# 05-Switch_SFP_CM4_RJ45.net
KiCad netlist of a schematic drawn in Altium Designer
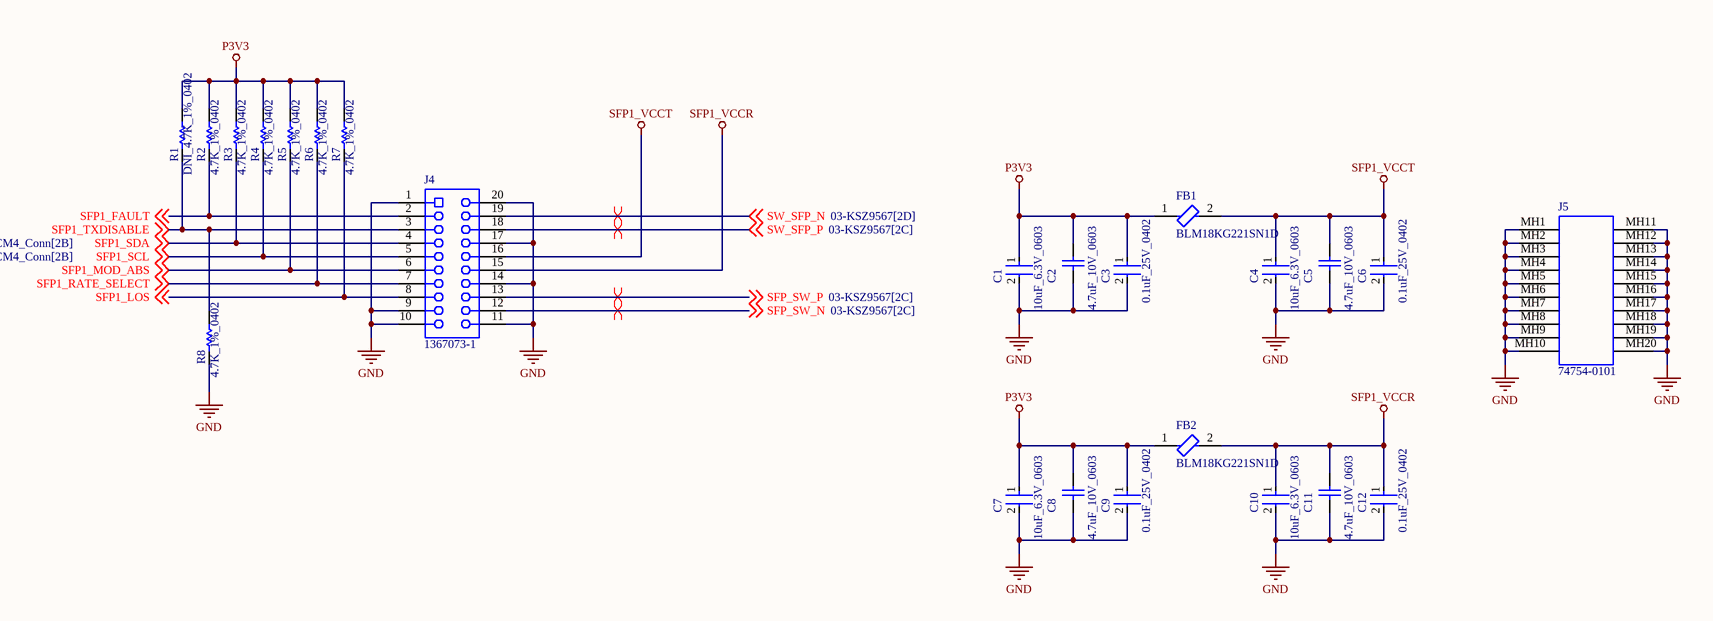
[diagram p0: 05-Switch_SFP_CM4_RJ45.SchDoc]

(export (version "E")
  (design (tool "Eeschema 10.0.6"))
  (components
    (comp (ref "C1")
      (value "10uF_6.3V_0603")
      (footprint "FP-C0603C106M9PACTU-MFG")
      (description "CAP CER 10UF 6.3V X5R 0603")
      (fields
        (field (name "MANUFACTURER PART NUMBER") "C0603C106M9PACTU")
        (field (name "MANUFACTURER") "Kemet")
      )
      (libsource (lib "Altium Content Vault") (part "b4654b650e69147ec39a6b967a45e02"))
    )
    (comp (ref "C2")
      (value "4.7uF_10V_0603")
      (footprint "CAPC1608X87X35NL15T15")
      (fields (field (name "PART NUMBER") "C0603C475K8PACTU") (field (name "MANUFACTURER") "Kemet"))
      (libsource (lib "Altium Content Vault") (part "CAP"))
    )
    (comp (ref "C3")
      (value "0.1uF_25V_0402")
      (footprint "FP-0402-L_1_0_1-W_0_5_0_1-IPC_C")
      (description "General Purpose Ceramic Capacitor, 0402, 100nF, 10%, X7R, 15%, 25V")
      (fields (field (name "VOLTAGE") "25V") (field (name "TOLERANCE") "10%"))
      (libsource (lib "Altium Content Vault") (part "b4654b650e69147ec39a6b967a45e02"))
    )
    (comp (ref "C4")
      (value "10uF_6.3V_0603")
      (footprint "FP-C0603C106M9PACTU-MFG")
      (description "CAP CER 10UF 6.3V X5R 0603")
      (fields
        (field (name "MANUFACTURER PART NUMBER") "C0603C106M9PACTU")
        (field (name "MANUFACTURER") "Kemet")
      )
      (libsource (lib "Altium Content Vault") (part "b4654b650e69147ec39a6b967a45e02"))
    )
    (comp (ref "C5")
      (value "4.7uF_10V_0603")
      (footprint "CAPC1608X87X35NL15T15")
      (fields (field (name "PART NUMBER") "C0603C475K8PACTU") (field (name "MANUFACTURER") "Kemet"))
      (libsource (lib "Altium Content Vault") (part "CAP"))
    )
    (comp (ref "C6")
      (value "0.1uF_25V_0402")
      (footprint "FP-0402-L_1_0_1-W_0_5_0_1-IPC_C")
      (description "General Purpose Ceramic Capacitor, 0402, 100nF, 10%, X7R, 15%, 25V")
      (fields (field (name "VOLTAGE") "25V") (field (name "TOLERANCE") "10%"))
      (libsource (lib "Altium Content Vault") (part "b4654b650e69147ec39a6b967a45e02"))
    )
    (comp (ref "C7")
      (value "10uF_6.3V_0603")
      (footprint "FP-C0603C106M9PACTU-MFG")
      (description "CAP CER 10UF 6.3V X5R 0603")
      (fields
        (field (name "MANUFACTURER PART NUMBER") "C0603C106M9PACTU")
        (field (name "MANUFACTURER") "Kemet")
      )
      (libsource (lib "Altium Content Vault") (part "b4654b650e69147ec39a6b967a45e02"))
    )
    (comp (ref "C8")
      (value "4.7uF_10V_0603")
      (footprint "CAPC1608X87X35NL15T15")
      (fields (field (name "PART NUMBER") "C0603C475K8PACTU") (field (name "MANUFACTURER") "Kemet"))
      (libsource (lib "Altium Content Vault") (part "CAP"))
    )
    (comp (ref "C9")
      (value "0.1uF_25V_0402")
      (footprint "FP-0402-L_1_0_1-W_0_5_0_1-IPC_C")
      (description "General Purpose Ceramic Capacitor, 0402, 100nF, 10%, X7R, 15%, 25V")
      (fields (field (name "VOLTAGE") "25V") (field (name "TOLERANCE") "10%"))
      (libsource (lib "Altium Content Vault") (part "b4654b650e69147ec39a6b967a45e02"))
    )
    (comp (ref "C10")
      (value "10uF_6.3V_0603")
      (footprint "FP-C0603C106M9PACTU-MFG")
      (description "CAP CER 10UF 6.3V X5R 0603")
      (fields
        (field (name "MANUFACTURER PART NUMBER") "C0603C106M9PACTU")
        (field (name "MANUFACTURER") "Kemet")
      )
      (libsource (lib "Altium Content Vault") (part "b4654b650e69147ec39a6b967a45e02"))
    )
    (comp (ref "C11")
      (value "4.7uF_10V_0603")
      (footprint "CAPC1608X87X35NL15T15")
      (fields (field (name "PART NUMBER") "C0603C475K8PACTU") (field (name "MANUFACTURER") "Kemet"))
      (libsource (lib "Altium Content Vault") (part "CAP"))
    )
    (comp (ref "C12")
      (value "0.1uF_25V_0402")
      (footprint "FP-0402-L_1_0_1-W_0_5_0_1-IPC_C")
      (description "General Purpose Ceramic Capacitor, 0402, 100nF, 10%, X7R, 15%, 25V")
      (fields (field (name "VOLTAGE") "25V") (field (name "TOLERANCE") "10%"))
      (libsource (lib "Altium Content Vault") (part "b4654b650e69147ec39a6b967a45e02"))
    )
    (comp (ref "FB1")
      (value "BLM18KG221SN1D")
      (footprint "FP-BLM18-0_15-t0_8-IPC_B")
      (description "Chip Ferrite Bead, 0603, 220Ω @ 100MHz, 0.05Ω, 25%, 2.2A")
      (fields (field (name "TOLERANCE") "25%"))
      (libsource (lib "Altium Content Vault") (part "5f30dd21d616792df468990f7003faa"))
    )
    (comp (ref "FB2")
      (value "BLM18KG221SN1D")
      (footprint "FP-BLM18-0_15-t0_8-IPC_B")
      (description "Chip Ferrite Bead, 0603, 220Ω @ 100MHz, 0.05Ω, 25%, 2.2A")
      (fields (field (name "TOLERANCE") "25%"))
      (libsource (lib "Altium Content Vault") (part "5f30dd21d616792df468990f7003faa"))
    )
    (comp (ref "J4")
      (value "1367073-1")
      (footprint "TECO-1367073-1_V")
      (fields (field (name "MANUFACTURER") "TE Connectivity"))
      (libsource (lib "Altium Content Vault") (part "CN-2P-F-R20_B"))
    )
    (comp (ref "J5")
      (value "74754-0101")
      (footprint "MOLX-74754-0101_V")
      (description "SFP+ Cage, Single Port, Height 10.85 mm, Tail Height 3.05 mm, -40 to 85 degC, RoHS, Tray")
      (libsource (lib "Altium Content Vault") (part "MOLX-74754-0101"))
    )
    (comp (ref "R1")
      (value "DNI_4.7K_1%_0402")
      (footprint "RESC1005X40X25NL10T10")
      (fields (field (name "MANUFACTURER") "Bourns") (field (name "PART NUMBER") "CR0402-FX-4701GLF"))
      (libsource (lib "Altium Content Vault") (part "RES"))
    )
    (comp (ref "R2")
      (value "4.7K_1%_0402")
      (footprint "RESC1005X40X25NL10T10")
      (fields (field (name "MANUFACTURER") "Bourns") (field (name "PART NUMBER") "CR0402-FX-4701GLF"))
      (libsource (lib "Altium Content Vault") (part "RES"))
    )
    (comp (ref "R3")
      (value "4.7K_1%_0402")
      (footprint "RESC1005X40X25NL10T10")
      (fields (field (name "MANUFACTURER") "Bourns") (field (name "PART NUMBER") "CR0402-FX-4701GLF"))
      (libsource (lib "Altium Content Vault") (part "RES"))
    )
    (comp (ref "R4")
      (value "4.7K_1%_0402")
      (footprint "RESC1005X40X25NL10T10")
      (fields (field (name "MANUFACTURER") "Bourns") (field (name "PART NUMBER") "CR0402-FX-4701GLF"))
      (libsource (lib "Altium Content Vault") (part "RES"))
    )
    (comp (ref "R5")
      (value "4.7K_1%_0402")
      (footprint "RESC1005X40X25NL10T10")
      (fields (field (name "MANUFACTURER") "Bourns") (field (name "PART NUMBER") "CR0402-FX-4701GLF"))
      (libsource (lib "Altium Content Vault") (part "RES"))
    )
    (comp (ref "R6")
      (value "4.7K_1%_0402")
      (footprint "RESC1005X40X25NL10T10")
      (fields (field (name "MANUFACTURER") "Bourns") (field (name "PART NUMBER") "CR0402-FX-4701GLF"))
      (libsource (lib "Altium Content Vault") (part "RES"))
    )
    (comp (ref "R7")
      (value "4.7K_1%_0402")
      (footprint "RESC1005X40X25NL10T10")
      (fields (field (name "MANUFACTURER") "Bourns") (field (name "PART NUMBER") "CR0402-FX-4701GLF"))
      (libsource (lib "Altium Content Vault") (part "RES"))
    )
    (comp (ref "R8")
      (value "4.7K_1%_0402")
      (footprint "RESC1005X40X25NL10T10")
      (fields (field (name "MANUFACTURER") "Bourns") (field (name "PART NUMBER") "CR0402-FX-4701GLF"))
      (libsource (lib "Altium Content Vault") (part "RES"))
    )
  )
  (nets
    (net (code "1") (name "GND") (class "Default")
      (node (ref "C1") (pin "2") (pinfunction "2_2") (pintype "passive"))
      (node (ref "C10") (pin "2") (pinfunction "2_2") (pintype "passive"))
      (node (ref "C11") (pin "1") (pinfunction "1_1") (pintype "passive"))
      (node (ref "C12") (pin "2") (pinfunction "2_2") (pintype "passive"))
      (node (ref "C2") (pin "1") (pinfunction "1_1") (pintype "passive"))
      (node (ref "C3") (pin "2") (pinfunction "2_2") (pintype "passive"))
      (node (ref "C4") (pin "2") (pinfunction "2_2") (pintype "passive"))
      (node (ref "C5") (pin "1") (pinfunction "1_1") (pintype "passive"))
      (node (ref "C6") (pin "2") (pinfunction "2_2") (pintype "passive"))
      (node (ref "C7") (pin "2") (pinfunction "2_2") (pintype "passive"))
      (node (ref "C8") (pin "1") (pinfunction "1_1") (pintype "passive"))
      (node (ref "C9") (pin "2") (pinfunction "2_2") (pintype "passive"))
      (node (ref "J4") (pin "1") (pinfunction "1_1") (pintype "passive"))
      (node (ref "J4") (pin "10") (pinfunction "10_10") (pintype "passive"))
      (node (ref "J4") (pin "11") (pinfunction "11_11") (pintype "passive"))
      (node (ref "J4") (pin "14") (pinfunction "14_14") (pintype "passive"))
      (node (ref "J4") (pin "17") (pinfunction "17_17") (pintype "passive"))
      (node (ref "J4") (pin "20") (pinfunction "20_20") (pintype "passive"))
      (node (ref "J4") (pin "9") (pinfunction "9_9") (pintype "passive"))
      (node (ref "J5") (pin "MH1") (pinfunction "MH1_MH1") (pintype "passive"))
      (node (ref "J5") (pin "MH10") (pinfunction "MH10_MH10") (pintype "passive"))
      (node (ref "J5") (pin "MH11") (pinfunction "MH11_MH11") (pintype "passive"))
      (node (ref "J5") (pin "MH12") (pinfunction "MH12_MH12") (pintype "passive"))
      (node (ref "J5") (pin "MH13") (pinfunction "MH13_MH13") (pintype "passive"))
      (node (ref "J5") (pin "MH14") (pinfunction "MH14_MH14") (pintype "passive"))
      (node (ref "J5") (pin "MH15") (pinfunction "MH15_MH15") (pintype "passive"))
      (node (ref "J5") (pin "MH16") (pinfunction "MH16_MH16") (pintype "passive"))
      (node (ref "J5") (pin "MH17") (pinfunction "MH17_MH17") (pintype "passive"))
      (node (ref "J5") (pin "MH18") (pinfunction "MH18_MH18") (pintype "passive"))
      (node (ref "J5") (pin "MH19") (pinfunction "MH19_MH19") (pintype "passive"))
      (node (ref "J5") (pin "MH2") (pinfunction "MH2_MH2") (pintype "passive"))
      (node (ref "J5") (pin "MH20") (pinfunction "MH20_MH20") (pintype "passive"))
      (node (ref "J5") (pin "MH3") (pinfunction "MH3_MH3") (pintype "passive"))
      (node (ref "J5") (pin "MH4") (pinfunction "MH4_MH4") (pintype "passive"))
      (node (ref "J5") (pin "MH5") (pinfunction "MH5_MH5") (pintype "passive"))
      (node (ref "J5") (pin "MH6") (pinfunction "MH6_MH6") (pintype "passive"))
      (node (ref "J5") (pin "MH7") (pinfunction "MH7_MH7") (pintype "passive"))
      (node (ref "J5") (pin "MH8") (pinfunction "MH8_MH8") (pintype "passive"))
      (node (ref "J5") (pin "MH9") (pinfunction "MH9_MH9") (pintype "passive"))
      (node (ref "R8") (pin "2") (pinfunction "2_2") (pintype "passive"))
    )
    (net (code "2") (name "P3V3") (class "Default")
      (node (ref "C1") (pin "1") (pinfunction "1_1") (pintype "passive"))
      (node (ref "C2") (pin "2") (pinfunction "2_2") (pintype "passive"))
      (node (ref "C3") (pin "1") (pinfunction "1_1") (pintype "passive"))
      (node (ref "C7") (pin "1") (pinfunction "1_1") (pintype "passive"))
      (node (ref "C8") (pin "2") (pinfunction "2_2") (pintype "passive"))
      (node (ref "C9") (pin "1") (pinfunction "1_1") (pintype "passive"))
      (node (ref "FB1") (pin "1") (pinfunction "1_1") (pintype "passive"))
      (node (ref "FB2") (pin "1") (pinfunction "1_1") (pintype "passive"))
      (node (ref "R1") (pin "1") (pinfunction "1_1") (pintype "passive"))
      (node (ref "R2") (pin "1") (pinfunction "1_1") (pintype "passive"))
      (node (ref "R3") (pin "1") (pinfunction "1_1") (pintype "passive"))
      (node (ref "R4") (pin "1") (pinfunction "1_1") (pintype "passive"))
      (node (ref "R5") (pin "1") (pinfunction "1_1") (pintype "passive"))
      (node (ref "R6") (pin "1") (pinfunction "1_1") (pintype "passive"))
      (node (ref "R7") (pin "1") (pinfunction "1_1") (pintype "passive"))
    )
    (net (code "3") (name "SFP1_FAULT") (class "Default")
      (node (ref "J4") (pin "2") (pinfunction "2_2") (pintype "passive"))
      (node (ref "R2") (pin "2") (pinfunction "2_2") (pintype "passive"))
    )
    (net (code "4") (name "SFP1_LOS") (class "Default")
      (node (ref "J4") (pin "8") (pinfunction "8_8") (pintype "passive"))
      (node (ref "R7") (pin "2") (pinfunction "2_2") (pintype "passive"))
    )
    (net (code "5") (name "SFP1_MOD_ABS") (class "Default")
      (node (ref "J4") (pin "6") (pinfunction "6_6") (pintype "passive"))
      (node (ref "R5") (pin "2") (pinfunction "2_2") (pintype "passive"))
    )
    (net (code "6") (name "SFP1_RATE_SELECT") (class "Default")
      (node (ref "J4") (pin "7") (pinfunction "7_7") (pintype "passive"))
      (node (ref "R6") (pin "2") (pinfunction "2_2") (pintype "passive"))
    )
    (net (code "7") (name "SFP1_SCL") (class "Default")
      (node (ref "J4") (pin "5") (pinfunction "5_5") (pintype "passive"))
      (node (ref "R4") (pin "2") (pinfunction "2_2") (pintype "passive"))
    )
    (net (code "8") (name "SFP1_SDA") (class "Default")
      (node (ref "J4") (pin "4") (pinfunction "4_4") (pintype "passive"))
      (node (ref "R3") (pin "2") (pinfunction "2_2") (pintype "passive"))
    )
    (net (code "9") (name "SFP1_TXDISABLE") (class "Default")
      (node (ref "J4") (pin "3") (pinfunction "3_3") (pintype "passive"))
      (node (ref "R1") (pin "2") (pinfunction "2_2") (pintype "passive"))
      (node (ref "R8") (pin "1") (pinfunction "1_1") (pintype "passive"))
    )
    (net (code "10") (name "SFP1_VCCR") (class "Default")
      (node (ref "C10") (pin "1") (pinfunction "1_1") (pintype "passive"))
      (node (ref "C11") (pin "2") (pinfunction "2_2") (pintype "passive"))
      (node (ref "C12") (pin "1") (pinfunction "1_1") (pintype "passive"))
      (node (ref "FB2") (pin "2") (pinfunction "2_2") (pintype "passive"))
      (node (ref "J4") (pin "15") (pinfunction "15_15") (pintype "passive"))
    )
    (net (code "11") (name "SFP1_VCCT") (class "Default")
      (node (ref "C4") (pin "1") (pinfunction "1_1") (pintype "passive"))
      (node (ref "C5") (pin "2") (pinfunction "2_2") (pintype "passive"))
      (node (ref "C6") (pin "1") (pinfunction "1_1") (pintype "passive"))
      (node (ref "FB1") (pin "2") (pinfunction "2_2") (pintype "passive"))
      (node (ref "J4") (pin "16") (pinfunction "16_16") (pintype "passive"))
    )
    (net (code "12") (name "SFP_SW_N") (class "Default")
      (node (ref "J4") (pin "12") (pinfunction "12_12") (pintype "passive"))
    )
    (net (code "13") (name "SFP_SW_P") (class "Default")
      (node (ref "J4") (pin "13") (pinfunction "13_13") (pintype "passive"))
    )
    (net (code "14") (name "SW_SFP_N") (class "Default")
      (node (ref "J4") (pin "19") (pinfunction "19_19") (pintype "passive"))
    )
    (net (code "15") (name "SW_SFP_P") (class "Default")
      (node (ref "J4") (pin "18") (pinfunction "18_18") (pintype "passive"))
    )
  )
)
